# RTD_Channel.net
KiCad netlist of a schematic drawn in Altium Designer
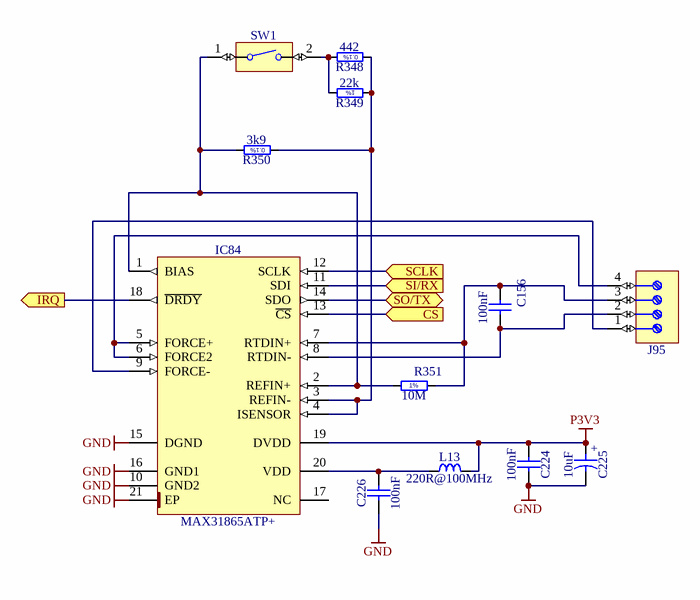
[diagram p0: RTD_Channel.SchDoc]

(export (version "E")
  (design (tool "Eeschema 10.0.6"))
  (components
    (comp (ref "C156")
      (value "100nF")
      (footprint "CAPC1005X55N")
      (description "Non-polarised capacitor")
      (fields
        (field (name "PART NUMBER") "CC0402_100NF_16V_10%_X5R")
        (field (name "VOLTAGE") "16V")
        (field (name "AUTHOR") "CERN DEM JLC")
      )
      (libsource (lib "Capacitors") (part "Capacitor - non polarized"))
    )
    (comp (ref "C224")
      (value "100nF")
      (footprint "CAPC1005X55N")
      (description "Non-polarised capacitor")
      (fields
        (field (name "PART NUMBER") "CC0402_100NF_16V_10%_X5R")
        (field (name "VOLTAGE") "16V")
        (field (name "AUTHOR") "CERN DEM JLC")
      )
      (libsource (lib "Capacitors") (part "Capacitor - non polarized"))
    )
    (comp (ref "C225")
      (value "10uF")
      (footprint "CAPMP3216X180N")
      (description "Polarised capacitor")
      (fields
        (field (name "PART NUMBER") "CTE3216-18_10UF_16V_20%_AVX_TCJ")
        (field (name "VOLTAGE") "16V")
        (field (name "AUTHOR") "CERN DEM JLC")
      )
      (libsource (lib "Capacitors") (part "Capacitor - polarized"))
    )
    (comp (ref "C226")
      (value "100nF")
      (footprint "CAPC1005X55N")
      (description "Non-polarised capacitor")
      (fields
        (field (name "PART NUMBER") "CC0402_100NF_16V_10%_X5R")
        (field (name "VOLTAGE") "16V")
        (field (name "AUTHOR") "CERN DEM JLC")
      )
      (libsource (lib "Capacitors") (part "Capacitor - non polarized"))
    )
    (comp (ref "IC84")
      (value "MAX31865ATP+")
      (footprint "QFN65P500X500X80-21N-S335")
      (description "RTD-to-Digital Converter")
      (fields (field (name "MANUFACTURER") "MAXIM") (field (name "AUTHOR") "CERN DEM MR"))
      (libsource (lib "ICs And Semiconductors") (part "MAX31865ATP+"))
    )
    (comp (ref "J95")
      (value "~")
      (footprint "PHOENIX_1725672")
      (description "Terminal Block, 4 Positions, Screw Connection")
      (fields
        (field (name "PART NUMBER") "PHOENIX_1725672")
        (field (name "MANUFACTURER") "PHOENIX CONTACT")
        (field (name "AUTHOR") "CERN DEM JMW")
      )
      (libsource (lib "Connectors") (part "Terminal Block_4 Positions_Screw Connection"))
    )
    (comp (ref "L13")
      (value "220R@100MHz")
      (footprint "INDC1005X55N")
      (description "Inductor")
      (fields
        (field (name "PART NUMBER") "IND0402_MURATA_BLM15HB221SN1")
        (field (name "POWER") "250mA")
        (field (name "AUTHOR") "CERN DEM JLC")
      )
      (libsource (lib "Inductors & Transformers") (part "Inductor"))
    )
    (comp (ref "R348")
      (value "442")
      (footprint "RESC1608X55N")
      (description "Resistor - 0.1%")
      (fields
        (field (name "PART NUMBER") "R0603_442R_0.1%_0.063W_25PPM")
        (field (name "POWER") "0.063W")
        (field (name "AUTHOR") "GK")
      )
      (libsource (lib "LIBRARY_SCH") (part "RES_0603_442R_0.1%_25ppm"))
    )
    (comp (ref "R349")
      (value "22k")
      (footprint "RESC1005X40N")
      (description "Resistor - 1%")
      (fields
        (field (name "PART NUMBER") "R0402_22K_1%_0.0625W_100PPM")
        (field (name "POWER") "0.0625W")
        (field (name "AUTHOR") "CERN DEM JLC")
      )
      (libsource (lib "Resistors") (part "Resistor - 1%"))
    )
    (comp (ref "R350")
      (value "3k9")
      (footprint "RESC1608X55N")
      (description "Resistor - 0.1%")
      (fields
        (field (name "PART NUMBER") "R0603_3k9_0.1%_0.063W_10PPM")
        (field (name "POWER") "0.063W")
        (field (name "AUTHOR") "GK")
      )
      (libsource (lib "LIBRARY_SCH") (part "RES_0603_3k9_0.1%_10ppm"))
    )
    (comp (ref "R351")
      (value "10M")
      (footprint "RESC1608X55N")
      (description "Resistor - 1%")
      (fields
        (field (name "PART NUMBER") "R0603_10M_1%_0.1W_100PPM")
        (field (name "POWER") "0.1W")
        (field (name "AUTHOR") "CERN DEM JLC")
      )
      (libsource (lib "Resistors") (part "Resistor - 1%"))
    )
    (comp (ref "SW1")
      (value "Switch")
      (footprint "SW_OMRON_A6SN-1101")
      (description "1 Ways SPST DIP Switch")
      (fields
        (field (name "PART NUMBER") "SW_OMRON_A6SN-1101")
        (field (name "MANUFACTURER") "OMRON")
        (field (name "AUTHOR") "CERN DEM JLC")
      )
      (libsource (lib "Eletro-mechanical") (part "SW 1x SPST DIP Switch"))
    )
  )
  (nets
    (net (code "1") (name "/CS") (class "Default")
      (node (ref "IC84") (pin "13") (pinfunction "~{CS}_13") (pintype "input"))
    )
    (net (code "2") (name "/IRQ") (class "Default")
      (node (ref "IC84") (pin "18") (pinfunction "~{DRDY}_18") (pintype "output"))
    )
    (net (code "3") (name "/SCLK") (class "Default")
      (node (ref "IC84") (pin "12") (pinfunction "SCLK_12") (pintype "input"))
    )
    (net (code "4") (name "/SI{slash}RX") (class "Default")
      (node (ref "IC84") (pin "11") (pinfunction "SDI_11") (pintype "input"))
    )
    (net (code "5") (name "/SO{slash}TX") (class "Default")
      (node (ref "IC84") (pin "14") (pinfunction "SDO_14") (pintype "output"))
    )
    (net (code "6") (name "GND") (class "Default")
      (node (ref "C224") (pin "2") (pinfunction "2_2") (pintype "passive"))
      (node (ref "C225") (pin "2") (pinfunction "2_2") (pintype "passive"))
      (node (ref "C226") (pin "1") (pinfunction "1_1") (pintype "passive"))
      (node (ref "IC84") (pin "10") (pinfunction "GND2_10") (pintype "power_in"))
      (node (ref "IC84") (pin "15") (pinfunction "DGND_15") (pintype "power_in"))
      (node (ref "IC84") (pin "16") (pinfunction "GND1_16") (pintype "power_in"))
      (node (ref "IC84") (pin "21") (pinfunction "EP_21") (pintype "power_in"))
    )
    (net (code "7") (name "Net-(IC84-BIAS)") (class "Default")
      (node (ref "IC84") (pin "1") (pinfunction "BIAS_1") (pintype "output"))
      (node (ref "IC84") (pin "2") (pinfunction "REFIN+_2") (pintype "input"))
      (node (ref "R350") (pin "2") (pinfunction "2_2") (pintype "passive"))
      (node (ref "R351") (pin "1") (pinfunction "1_1") (pintype "passive"))
      (node (ref "SW1") (pin "1") (pinfunction "1_1") (pintype "bidirectional"))
    )
    (net (code "8") (name "Net-(IC84-FORCE+)") (class "Default")
      (node (ref "IC84") (pin "5") (pinfunction "FORCE+_5") (pintype "input"))
      (node (ref "IC84") (pin "6") (pinfunction "FORCE2_6") (pintype "input"))
      (node (ref "J95") (pin "4") (pinfunction "4_4") (pintype "bidirectional"))
    )
    (net (code "9") (name "Net-(IC84-FORCE-)") (class "Default")
      (node (ref "IC84") (pin "9") (pinfunction "FORCE-_9") (pintype "input"))
      (node (ref "J95") (pin "1") (pinfunction "1_1") (pintype "bidirectional"))
    )
    (net (code "10") (name "Net-(IC84-ISENSOR)") (class "Default")
      (node (ref "IC84") (pin "3") (pinfunction "REFIN-_3") (pintype "input"))
      (node (ref "IC84") (pin "4") (pinfunction "ISENSOR_4") (pintype "input"))
      (node (ref "R348") (pin "1") (pinfunction "1_1") (pintype "passive"))
      (node (ref "R349") (pin "1") (pinfunction "1_1") (pintype "passive"))
      (node (ref "R350") (pin "1") (pinfunction "1_1") (pintype "passive"))
    )
    (net (code "11") (name "Net-(IC84-RTDIN+)") (class "Default")
      (node (ref "C156") (pin "1") (pinfunction "1_1") (pintype "passive"))
      (node (ref "IC84") (pin "7") (pinfunction "RTDIN+_7") (pintype "input"))
      (node (ref "J95") (pin "3") (pinfunction "3_3") (pintype "bidirectional"))
      (node (ref "R351") (pin "2") (pinfunction "2_2") (pintype "passive"))
    )
    (net (code "12") (name "Net-(IC84-RTDIN-)") (class "Default")
      (node (ref "C156") (pin "2") (pinfunction "2_2") (pintype "passive"))
      (node (ref "IC84") (pin "8") (pinfunction "RTDIN-_8") (pintype "input"))
      (node (ref "J95") (pin "2") (pinfunction "2_2") (pintype "bidirectional"))
    )
    (net (code "13") (name "Net-(IC84-VDD)") (class "Default")
      (node (ref "C226") (pin "2") (pinfunction "2_2") (pintype "passive"))
      (node (ref "IC84") (pin "20") (pinfunction "VDD_20") (pintype "power_in"))
      (node (ref "L13") (pin "1") (pinfunction "1_1") (pintype "passive"))
    )
    (net (code "14") (name "Net-(R348-Pad2)") (class "Default")
      (node (ref "R348") (pin "2") (pinfunction "2_2") (pintype "passive"))
      (node (ref "R349") (pin "2") (pinfunction "2_2") (pintype "passive"))
      (node (ref "SW1") (pin "2") (pinfunction "2_2") (pintype "bidirectional"))
    )
    (net (code "15") (name "P3V3") (class "Default")
      (node (ref "C224") (pin "1") (pinfunction "1_1") (pintype "passive"))
      (node (ref "C225") (pin "1") (pinfunction "1_1") (pintype "passive"))
      (node (ref "IC84") (pin "19") (pinfunction "DVDD_19") (pintype "power_in"))
      (node (ref "L13") (pin "2") (pinfunction "2_2") (pintype "passive"))
    )
    (net (code "16") (name "unconnected-(IC84-NC-Pad17)") (class "Default")
      (node (ref "IC84") (pin "17") (pinfunction "NC_17") (pintype "passive"))
    )
  )
)
